# driver_section.net
KiCad netlist of a schematic drawn in Altium Designer
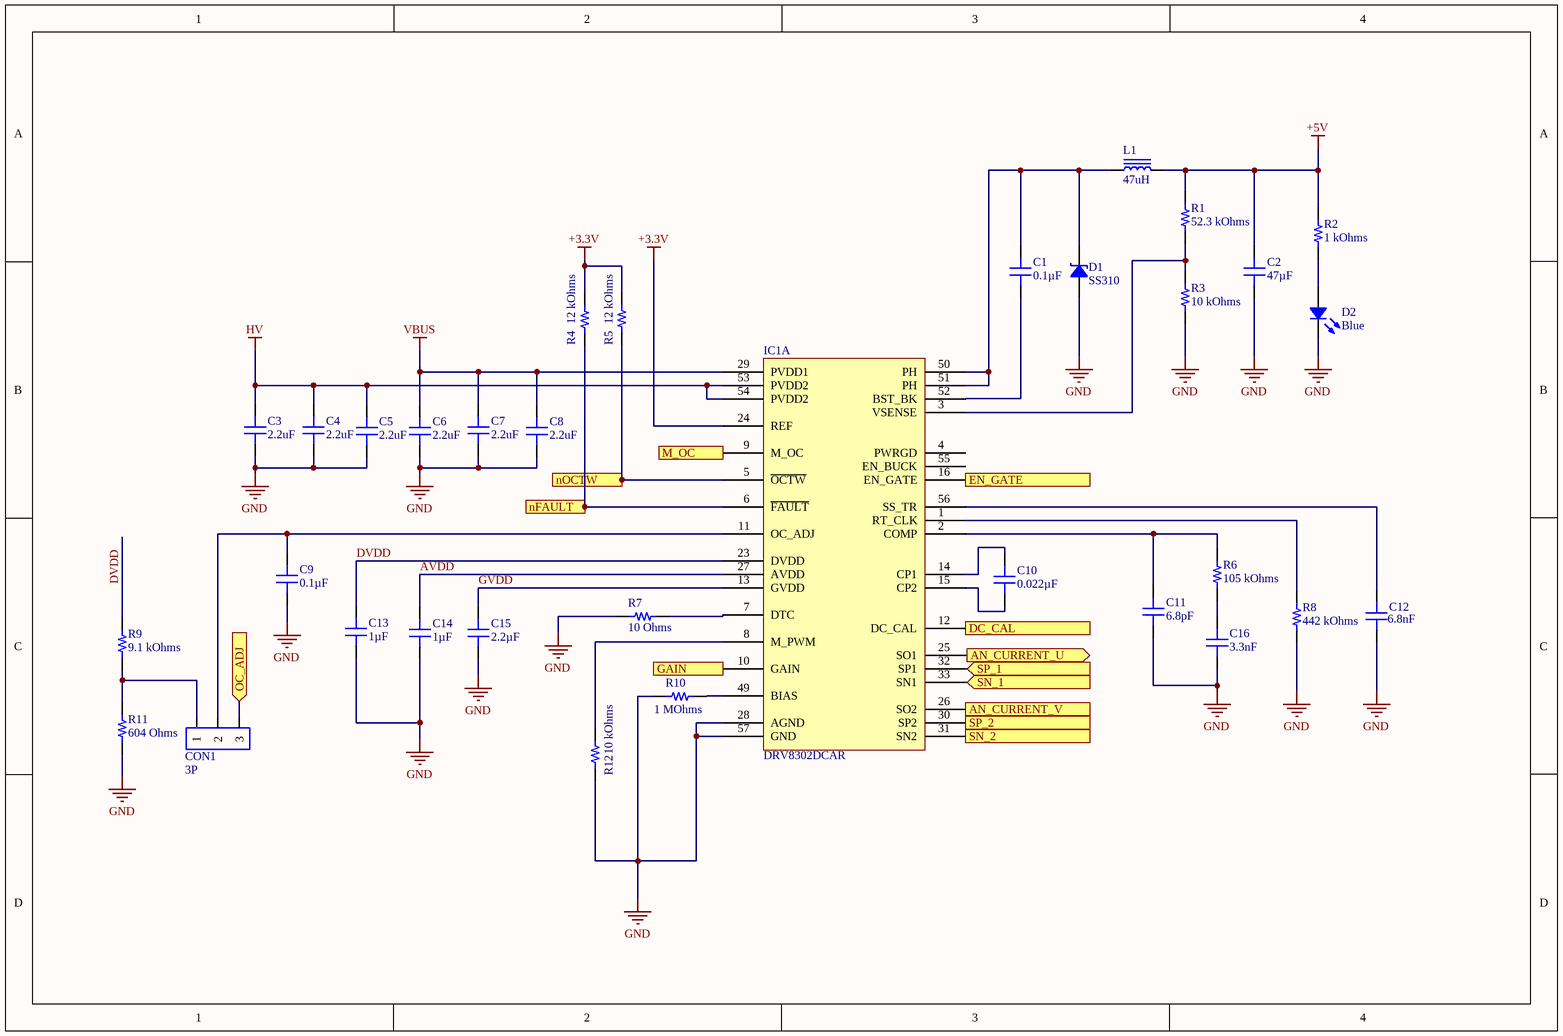
[diagram p0: driver section.SchDoc]

(export (version "E")
  (design (tool "Eeschema 10.0.6"))
  (components
    (comp (ref "C1")
      (value "0.1µF")
      (footprint "CAP 0402_1005")
      (description "CAP CER 0.1UF 16V X7R 0402")
      (fields (field (name "PART NUMBER") "C0402C104M4RACTU") (field (name "MANUFACTURER") "KEMET"))
      (libsource (lib "Celestial Altium Library - altium_library") (part "Capacitor"))
    )
    (comp (ref "C2")
      (value "47µF")
      (footprint "CAP 1210_3225 - 2.8MM")
      (description "CAP CER 47UF 16V X6S 1210")
      (fields
        (field (name "PART NUMBER") "GRM32EC81C476KE15L")
        (field (name "MANUFACTURER") "Murata Electronics")
      )
      (libsource (lib "Celestial Altium Library - altium_library") (part "Capacitor"))
    )
    (comp (ref "C3")
      (value "2.2uF")
      (footprint "CAP FILM 1210")
      (description "CAP FILM 0.022UF 5% 100VDC 1210")
      (fields
        (field (name "PART NUMBER") "LDEEB2220JA0N00")
        (field (name "CAPACITANCE") "2.2uF")
        (field (name "MANUFACTURER") "KEMET")
      )
      (libsource (lib "Celestial Altium Library - altium_library") (part "Capacitor"))
    )
    (comp (ref "C4")
      (value "2.2uF")
      (footprint "CAP FILM 1210")
      (description "CAP FILM 0.022UF 5% 100VDC 1210")
      (fields
        (field (name "PART NUMBER") "LDEEB2220JA0N00")
        (field (name "CAPACITANCE") "2.2uF")
        (field (name "MANUFACTURER") "KEMET")
      )
      (libsource (lib "Celestial Altium Library - altium_library") (part "Capacitor"))
    )
    (comp (ref "C5")
      (value "2.2uF")
      (footprint "CAP FILM 1210")
      (description "CAP FILM 0.022UF 5% 100VDC 1210")
      (fields
        (field (name "PART NUMBER") "LDEEB2220JA0N00")
        (field (name "CAPACITANCE") "2.2uF")
        (field (name "MANUFACTURER") "KEMET")
      )
      (libsource (lib "Celestial Altium Library - altium_library") (part "Capacitor"))
    )
    (comp (ref "C6")
      (value "2.2uF")
      (footprint "CAP FILM 1210")
      (description "CAP FILM 0.022UF 5% 100VDC 1210")
      (fields
        (field (name "PART NUMBER") "LDEEB2220JA0N00")
        (field (name "CAPACITANCE") "2.2uF")
        (field (name "MANUFACTURER") "KEMET")
      )
      (libsource (lib "Celestial Altium Library - altium_library") (part "Capacitor"))
    )
    (comp (ref "C7")
      (value "2.2uF")
      (footprint "CAP FILM 1210")
      (description "CAP FILM 0.022UF 5% 100VDC 1210")
      (fields
        (field (name "PART NUMBER") "LDEEB2220JA0N00")
        (field (name "CAPACITANCE") "2.2uF")
        (field (name "MANUFACTURER") "KEMET")
      )
      (libsource (lib "Celestial Altium Library - altium_library") (part "Capacitor"))
    )
    (comp (ref "C8")
      (value "2.2uF")
      (footprint "CAP FILM 1210")
      (description "CAP FILM 0.022UF 5% 100VDC 1210")
      (fields
        (field (name "PART NUMBER") "LDEEB2220JA0N00")
        (field (name "CAPACITANCE") "2.2uF")
        (field (name "MANUFACTURER") "KEMET")
      )
      (libsource (lib "Celestial Altium Library - altium_library") (part "Capacitor"))
    )
    (comp (ref "C9")
      (value "0.1µF")
      (footprint "CAP 0402_1005")
      (description "CAP CER 0.1UF 16V X7R 0402")
      (fields (field (name "PART NUMBER") "C0402C104M4RACTU") (field (name "MANUFACTURER") "KEMET"))
      (libsource (lib "Celestial Altium Library - altium_library") (part "Capacitor"))
    )
    (comp (ref "C10")
      (value "0.022µF")
      (footprint "CAP 0805_2012")
      (description "CAP CER 0.022UF 100V X7R 0805")
      (fields
        (field (name "PART NUMBER") "CL21B223KCFNNNE")
        (field (name "MANUFACTURER") "Samsung Electro-Mechanics")
      )
      (libsource (lib "Celestial Altium Library - altium_library") (part "Capacitor"))
    )
    (comp (ref "C11")
      (value "6.8pF")
      (footprint "CAP 0402_1005")
      (description "CAP CER 6.8PF 50V C0G/NP0 0402")
      (fields (field (name "PART NUMBER") "C0402C689C5GACAUTO") (field (name "MANUFACTURER") "KEMET"))
      (libsource (lib "Celestial Altium Library - altium_library") (part "Capacitor"))
    )
    (comp (ref "C12")
      (value "6.8nF")
      (footprint "CAP 0402_1005")
      (description "CAP CER 0.068UF 50V X7R 0402")
      (fields
        (field (name "PART NUMBER") "CGA2B3X7R1H683K050BB")
        (field (name "MANUFACTURER") "TDK Corporation")
      )
      (libsource (lib "Celestial Altium Library - altium_library") (part "Capacitor"))
    )
    (comp (ref "C13")
      (value "1µF")
      (footprint "CAP 0402_1005")
      (description "CAP CER 1UF 10V X7S 0402")
      (fields
        (field (name "PART NUMBER") "GRM155C71A105KE11D")
        (field (name "MANUFACTURER") "Murata Electronics")
      )
      (libsource (lib "Celestial Altium Library - altium_library") (part "Capacitor"))
    )
    (comp (ref "C14")
      (value "1µF")
      (footprint "CAP 0402_1005")
      (description "CAP CER 1UF 10V X7S 0402")
      (fields
        (field (name "PART NUMBER") "GRM155C71A105KE11D")
        (field (name "MANUFACTURER") "Murata Electronics")
      )
      (libsource (lib "Celestial Altium Library - altium_library") (part "Capacitor"))
    )
    (comp (ref "C15")
      (value "2.2µF")
      (footprint "CAP 0805_2012")
      (description "CAP CER 2.2UF 25V X7R 0805")
      (fields
        (field (name "PART NUMBER") "C2012X7R1E225M085AB")
        (field (name "MANUFACTURER") "TDK Corporation")
      )
      (libsource (lib "Celestial Altium Library - altium_library") (part "Capacitor"))
    )
    (comp (ref "C16")
      (value "3.3nF")
      (footprint "CAP 0603_1608")
      (description "CAP CER 0.033UF 50V X7R 0603")
      (fields (field (name "PART NUMBER") "C0603C333K5RACAUTO") (field (name "MANUFACTURER") "KEMET"))
      (libsource (lib "Celestial Altium Library - altium_library") (part "Capacitor"))
    )
    (comp (ref "CON1")
      (value "3P")
      (footprint "Single_THT_3P_2.54Pitch_6Height_180C")
      (libsource (lib "My_Library_Header") (part "Single 3P 2.54mm"))
    )
    (comp (ref "D1")
      (value "SS310")
      (footprint "DO214AA SMB")
      (description "Zener Diode")
      (libsource (lib "My_Library_SMD_Zener_Diode") (part "SS310"))
    )
    (comp (ref "D2")
      (value "Blue")
      (footprint "LED 1206_3216 BLUE")
      (description "LED BLUE CLEAR 1206 SMD")
      (fields (field (name "PART NUMBER") "SM1206NBWC-IL") (field (name "MANUFACTURER") "Bivar Inc."))
      (libsource (lib "Celestial Altium Library - altium_library") (part "LED"))
    )
    (comp (ref "IC1")
      (value "DRV8302DCAR")
      (footprint "TI HTSSOP-56 DCA")
      (description "IC MOTOR DRIVER 8V-60V 56HTSSOP")
      (fields (field (name "MANUFACTURER") "Texas Instruments"))
      (libsource (lib "Celestial Altium Library - altium_library") (part "TI DRV8302"))
    )
    (comp (ref "L1")
      (value "47uH")
      (footprint "INDP100100X45N")
      (description "SMT Inductor")
      (libsource (lib "My_Library_Fixed_Inductor") (part "SRI1004-470M"))
    )
    (comp (ref "R1")
      (value "52.3 kOhms")
      (footprint "RES 1206_3216")
      (description "RES SMD 52.3K OHM 1% 1/4W 1206")
      (fields (field (name "PART NUMBER") "RC1206FR-0752K3L") (field (name "MANUFACTURER") "Yageo"))
      (libsource (lib "Celestial Altium Library - altium_library") (part "Resistor"))
    )
    (comp (ref "R2")
      (value "1 kOhms")
      (footprint "RES 1206_3216")
      (description "RES SMD 1K OHM 1% 1/4W 1206")
      (fields (field (name "PART NUMBER") "RC1206FR-071KL") (field (name "MANUFACTURER") "Yageo"))
      (libsource (lib "Celestial Altium Library - altium_library") (part "Resistor"))
    )
    (comp (ref "R3")
      (value "10 kOhms")
      (footprint "RES 1206_3216")
      (description "RES SMD 10K OHM 1% 1/4W 1206")
      (fields
        (field (name "PART NUMBER") "CRG1206F10K")
        (field (name "MANUFACTURER") "TE Connectivity Passive Product")
      )
      (libsource (lib "Celestial Altium Library - altium_library") (part "Resistor"))
    )
    (comp (ref "R4")
      (value "12 kOhms")
      (footprint "RES 1206_3216")
      (description "RES 12K OHM 1% 1/4W 1206")
      (fields
        (field (name "PART NUMBER") "RMCF1206FT12K0")
        (field (name "MANUFACTURER") "Stackpole Electronics Inc")
      )
      (libsource (lib "Celestial Altium Library - altium_library") (part "Resistor"))
    )
    (comp (ref "R5")
      (value "12 kOhms")
      (footprint "RES 1206_3216")
      (description "RES 12K OHM 1% 1/4W 1206")
      (fields
        (field (name "PART NUMBER") "RMCF1206FT12K0")
        (field (name "MANUFACTURER") "Stackpole Electronics Inc")
      )
      (libsource (lib "Celestial Altium Library - altium_library") (part "Resistor"))
    )
    (comp (ref "R6")
      (value "105 kOhms")
      (footprint "RES 1206_3216")
      (description "RES SMD 105K OHM 1% 1/4W 1206")
      (fields (field (name "PART NUMBER") "RC1206FR-07105KL") (field (name "MANUFACTURER") "Yageo"))
      (libsource (lib "Celestial Altium Library - altium_library") (part "Resistor"))
    )
    (comp (ref "R7")
      (value "10 Ohms")
      (footprint "RES 1206_3216")
      (description "CRGCQ 1206 10R 1%")
      (fields
        (field (name "PART NUMBER") "CRGCQ1206F10R")
        (field (name "MANUFACTURER") "TE Connectivity Passive Product")
      )
      (libsource (lib "Celestial Altium Library - altium_library") (part "Resistor"))
    )
    (comp (ref "R8")
      (value "442 kOhms")
      (footprint "RES 1206_3216")
      (description "RES SMD 442K OHM 1% 1/4W 1206")
      (fields (field (name "PART NUMBER") "CRCW1206442KFKEA") (field (name "MANUFACTURER") "Vishay Dale"))
      (libsource (lib "Celestial Altium Library - altium_library") (part "Resistor"))
    )
    (comp (ref "R9")
      (value "9.1 kOhms")
      (footprint "RES 1206_3216")
      (description "RES 9.1K OHM 1% 1/4W 1206")
      (fields
        (field (name "PART NUMBER") "RK73H2BTTD9101F")
        (field (name "MANUFACTURER") "KOA Speer Electronics, Inc.")
      )
      (libsource (lib "Celestial Altium Library - altium_library") (part "Resistor"))
    )
    (comp (ref "R10")
      (value "1 MOhms")
      (footprint "RES 1206_3216")
      (description "RES SMD 1M OHM 1% 1/4W 1206")
      (fields
        (field (name "PART NUMBER") "CRG1206F1M0")
        (field (name "MANUFACTURER") "TE Connectivity Passive Product")
      )
      (libsource (lib "Celestial Altium Library - altium_library") (part "Resistor"))
    )
    (comp (ref "R11")
      (value "604 Ohms")
      (footprint "RES 1206_3216")
      (description "RES SMD 604 OHM 1% 1/4W 1206")
      (fields (field (name "PART NUMBER") "KTR18EZPF6040") (field (name "MANUFACTURER") "Rohm Semiconductor"))
      (libsource (lib "Celestial Altium Library - altium_library") (part "Resistor"))
    )
    (comp (ref "R12")
      (value "10 kOhms")
      (footprint "RES 1206_3216")
      (description "RES SMD 10K OHM 1% 1/4W 1206")
      (fields
        (field (name "PART NUMBER") "CRG1206F10K")
        (field (name "MANUFACTURER") "TE Connectivity Passive Product")
      )
      (libsource (lib "Celestial Altium Library - altium_library") (part "Resistor"))
    )
  )
  (nets
    (net (code "1") (name "+3.3V") (class "Default")
      (node (ref "IC1") (pin "24") (pinfunction "REF_24") (pintype "passive"))
      (node (ref "R4") (pin "2") (pinfunction "2_2") (pintype "passive"))
      (node (ref "R5") (pin "2") (pinfunction "2_2") (pintype "passive"))
    )
    (net (code "2") (name "+5V") (class "Default")
      (node (ref "C2") (pin "2") (pinfunction "2_2") (pintype "passive"))
      (node (ref "L1") (pin "2") (pinfunction "2_2") (pintype "passive"))
      (node (ref "R1") (pin "2") (pinfunction "2_2") (pintype "passive"))
      (node (ref "R2") (pin "2") (pinfunction "2_2") (pintype "passive"))
    )
    (net (code "3") (name "/AN_CURRENT_U") (class "Default")
      (node (ref "IC1") (pin "25") (pinfunction "SO1_25") (pintype "passive"))
    )
    (net (code "4") (name "/AN_CURRENT_V") (class "Default")
      (node (ref "IC1") (pin "26") (pinfunction "SO2_26") (pintype "passive"))
    )
    (net (code "5") (name "/AVDD") (class "Default")
      (node (ref "C14") (pin "2") (pinfunction "2_2") (pintype "passive"))
      (node (ref "IC1") (pin "27") (pinfunction "AVDD_27") (pintype "passive"))
    )
    (net (code "6") (name "/DC_CAL") (class "Default")
      (node (ref "IC1") (pin "12") (pinfunction "DC_CAL_12") (pintype "passive"))
    )
    (net (code "7") (name "/DVDD") (class "Default")
      (node (ref "C13") (pin "2") (pinfunction "2_2") (pintype "passive"))
      (node (ref "IC1") (pin "23") (pinfunction "DVDD_23") (pintype "passive"))
      (node (ref "R9") (pin "2") (pinfunction "2_2") (pintype "passive"))
    )
    (net (code "8") (name "/EN_GATE") (class "Default")
      (node (ref "IC1") (pin "16") (pinfunction "EN_GATE_16") (pintype "passive"))
    )
    (net (code "9") (name "/GAIN") (class "Default")
      (node (ref "IC1") (pin "10") (pinfunction "GAIN_10") (pintype "passive"))
    )
    (net (code "10") (name "/GVDD") (class "Default")
      (node (ref "C15") (pin "2") (pinfunction "2_2") (pintype "passive"))
      (node (ref "IC1") (pin "13") (pinfunction "GVDD_13") (pintype "passive"))
    )
    (net (code "11") (name "/M_OC") (class "Default")
      (node (ref "IC1") (pin "9") (pinfunction "M_OC_9") (pintype "passive"))
    )
    (net (code "12") (name "/OC_ADJ") (class "Default")
      (node (ref "CON1") (pin "3") (pinfunction "3_3") (pintype "passive"))
    )
    (net (code "13") (name "/SN_1") (class "Default")
      (node (ref "IC1") (pin "33") (pinfunction "SN1_33") (pintype "passive"))
    )
    (net (code "14") (name "/SN_2") (class "Default")
      (node (ref "IC1") (pin "31") (pinfunction "SN2_31") (pintype "passive"))
    )
    (net (code "15") (name "/SP_1") (class "Default")
      (node (ref "IC1") (pin "32") (pinfunction "SP1_32") (pintype "passive"))
    )
    (net (code "16") (name "/SP_2") (class "Default")
      (node (ref "IC1") (pin "30") (pinfunction "SP2_30") (pintype "passive"))
    )
    (net (code "17") (name "/nFAULT") (class "Default")
      (node (ref "IC1") (pin "6") (pinfunction "~{FAULT}_6") (pintype "passive"))
      (node (ref "R4") (pin "1") (pinfunction "1_1") (pintype "passive"))
    )
    (net (code "18") (name "/nOCTW") (class "Default")
      (node (ref "IC1") (pin "5") (pinfunction "~{OCTW}_5") (pintype "passive"))
      (node (ref "R5") (pin "1") (pinfunction "1_1") (pintype "passive"))
    )
    (net (code "19") (name "GND") (class "Default")
      (node (ref "C11") (pin "1") (pinfunction "1_1") (pintype "passive"))
      (node (ref "C12") (pin "1") (pinfunction "1_1") (pintype "passive"))
      (node (ref "C13") (pin "1") (pinfunction "1_1") (pintype "passive"))
      (node (ref "C14") (pin "1") (pinfunction "1_1") (pintype "passive"))
      (node (ref "C15") (pin "1") (pinfunction "1_1") (pintype "passive"))
      (node (ref "C16") (pin "1") (pinfunction "1_1") (pintype "passive"))
      (node (ref "C2") (pin "1") (pinfunction "1_1") (pintype "passive"))
      (node (ref "C3") (pin "1") (pinfunction "1_1") (pintype "passive"))
      (node (ref "C4") (pin "1") (pinfunction "1_1") (pintype "passive"))
      (node (ref "C5") (pin "1") (pinfunction "1_1") (pintype "passive"))
      (node (ref "C6") (pin "1") (pinfunction "1_1") (pintype "passive"))
      (node (ref "C7") (pin "1") (pinfunction "1_1") (pintype "passive"))
      (node (ref "C8") (pin "1") (pinfunction "1_1") (pintype "passive"))
      (node (ref "C9") (pin "1") (pinfunction "1_1") (pintype "passive"))
      (node (ref "D1") (pin "1") (pinfunction "1_1") (pintype "passive"))
      (node (ref "D2") (pin "2") (pinfunction "2_2") (pintype "passive"))
      (node (ref "IC1") (pin "28") (pinfunction "AGND_28") (pintype "passive"))
      (node (ref "IC1") (pin "57") (pinfunction "GND_57") (pintype "passive"))
      (node (ref "R10") (pin "2") (pinfunction "2_2") (pintype "passive"))
      (node (ref "R11") (pin "1") (pinfunction "1_1") (pintype "passive"))
      (node (ref "R12") (pin "1") (pinfunction "1_1") (pintype "passive"))
      (node (ref "R3") (pin "1") (pinfunction "1_1") (pintype "passive"))
      (node (ref "R7") (pin "1") (pinfunction "1_1") (pintype "passive"))
      (node (ref "R8") (pin "1") (pinfunction "1_1") (pintype "passive"))
    )
    (net (code "20") (name "HV") (class "Default")
      (node (ref "C3") (pin "2") (pinfunction "2_2") (pintype "passive"))
      (node (ref "C4") (pin "2") (pinfunction "2_2") (pintype "passive"))
      (node (ref "C5") (pin "2") (pinfunction "2_2") (pintype "passive"))
      (node (ref "IC1") (pin "53") (pinfunction "PVDD2_53") (pintype "passive"))
      (node (ref "IC1") (pin "54") (pinfunction "PVDD2_54") (pintype "passive"))
    )
    (net (code "21") (name "Net-(C1-Pad2)") (class "Default")
      (node (ref "C1") (pin "2") (pinfunction "2_2") (pintype "passive"))
      (node (ref "D1") (pin "2") (pinfunction "2_2") (pintype "passive"))
      (node (ref "IC1") (pin "50") (pinfunction "PH_50") (pintype "passive"))
      (node (ref "IC1") (pin "51") (pinfunction "PH_51") (pintype "passive"))
      (node (ref "L1") (pin "1") (pinfunction "1_1") (pintype "passive"))
    )
    (net (code "22") (name "Net-(C16-Pad2)") (class "Default")
      (node (ref "C16") (pin "2") (pinfunction "2_2") (pintype "passive"))
      (node (ref "R6") (pin "1") (pinfunction "1_1") (pintype "passive"))
    )
    (net (code "23") (name "Net-(CON1-Pad1)") (class "Default")
      (node (ref "CON1") (pin "1") (pinfunction "1_1") (pintype "passive"))
      (node (ref "R11") (pin "2") (pinfunction "2_2") (pintype "passive"))
      (node (ref "R9") (pin "1") (pinfunction "1_1") (pintype "passive"))
    )
    (net (code "24") (name "Net-(D2-Pad1)") (class "Default")
      (node (ref "D2") (pin "1") (pinfunction "1_1") (pintype "passive"))
      (node (ref "R2") (pin "1") (pinfunction "1_1") (pintype "passive"))
    )
    (net (code "25") (name "Net-(IC1A-BIAS)") (class "Default")
      (node (ref "IC1") (pin "49") (pinfunction "BIAS_49") (pintype "passive"))
      (node (ref "R10") (pin "1") (pinfunction "1_1") (pintype "passive"))
    )
    (net (code "26") (name "Net-(IC1A-BST_BK)") (class "Default")
      (node (ref "C1") (pin "1") (pinfunction "1_1") (pintype "passive"))
      (node (ref "IC1") (pin "52") (pinfunction "BST_BK_52") (pintype "passive"))
    )
    (net (code "27") (name "Net-(IC1A-COMP)") (class "Default")
      (node (ref "C11") (pin "2") (pinfunction "2_2") (pintype "passive"))
      (node (ref "IC1") (pin "2") (pinfunction "COMP_2") (pintype "passive"))
      (node (ref "R6") (pin "2") (pinfunction "2_2") (pintype "passive"))
    )
    (net (code "28") (name "Net-(IC1A-CP1)") (class "Default")
      (node (ref "C10") (pin "2") (pinfunction "2_2") (pintype "passive"))
      (node (ref "IC1") (pin "14") (pinfunction "CP1_14") (pintype "passive"))
    )
    (net (code "29") (name "Net-(IC1A-CP2)") (class "Default")
      (node (ref "C10") (pin "1") (pinfunction "1_1") (pintype "passive"))
      (node (ref "IC1") (pin "15") (pinfunction "CP2_15") (pintype "passive"))
    )
    (net (code "30") (name "Net-(IC1A-DTC)") (class "Default")
      (node (ref "IC1") (pin "7") (pinfunction "DTC_7") (pintype "passive"))
      (node (ref "R7") (pin "2") (pinfunction "2_2") (pintype "passive"))
    )
    (net (code "31") (name "Net-(IC1A-M_PWM)") (class "Default")
      (node (ref "IC1") (pin "8") (pinfunction "M_PWM_8") (pintype "passive"))
      (node (ref "R12") (pin "2") (pinfunction "2_2") (pintype "passive"))
    )
    (net (code "32") (name "Net-(IC1A-OC_ADJ)") (class "Default")
      (node (ref "C9") (pin "2") (pinfunction "2_2") (pintype "passive"))
      (node (ref "CON1") (pin "2") (pinfunction "2_2") (pintype "passive"))
      (node (ref "IC1") (pin "11") (pinfunction "OC_ADJ_11") (pintype "passive"))
    )
    (net (code "33") (name "Net-(IC1A-RT_CLK)") (class "Default")
      (node (ref "IC1") (pin "1") (pinfunction "RT_CLK_1") (pintype "passive"))
      (node (ref "R8") (pin "2") (pinfunction "2_2") (pintype "passive"))
    )
    (net (code "34") (name "Net-(IC1A-SS_TR)") (class "Default")
      (node (ref "C12") (pin "2") (pinfunction "2_2") (pintype "passive"))
      (node (ref "IC1") (pin "56") (pinfunction "SS_TR_56") (pintype "passive"))
    )
    (net (code "35") (name "Net-(IC1A-VSENSE)") (class "Default")
      (node (ref "IC1") (pin "3") (pinfunction "VSENSE_3") (pintype "passive"))
      (node (ref "R1") (pin "1") (pinfunction "1_1") (pintype "passive"))
      (node (ref "R3") (pin "2") (pinfunction "2_2") (pintype "passive"))
    )
    (net (code "36") (name "VBUS") (class "Default")
      (node (ref "C6") (pin "2") (pinfunction "2_2") (pintype "passive"))
      (node (ref "C7") (pin "2") (pinfunction "2_2") (pintype "passive"))
      (node (ref "C8") (pin "2") (pinfunction "2_2") (pintype "passive"))
      (node (ref "IC1") (pin "29") (pinfunction "PVDD1_29") (pintype "passive"))
    )
    (net (code "37") (name "unconnected-(IC1A-EN_BUCK-Pad55)") (class "Default")
      (node (ref "IC1") (pin "55") (pinfunction "EN_BUCK_55") (pintype "passive"))
    )
    (net (code "38") (name "unconnected-(IC1A-PWRGD-Pad4)") (class "Default")
      (node (ref "IC1") (pin "4") (pinfunction "PWRGD_4") (pintype "passive"))
    )
  )
)
